# baterry_tester.net
KiCad netlist of a schematic drawn in EAGLE
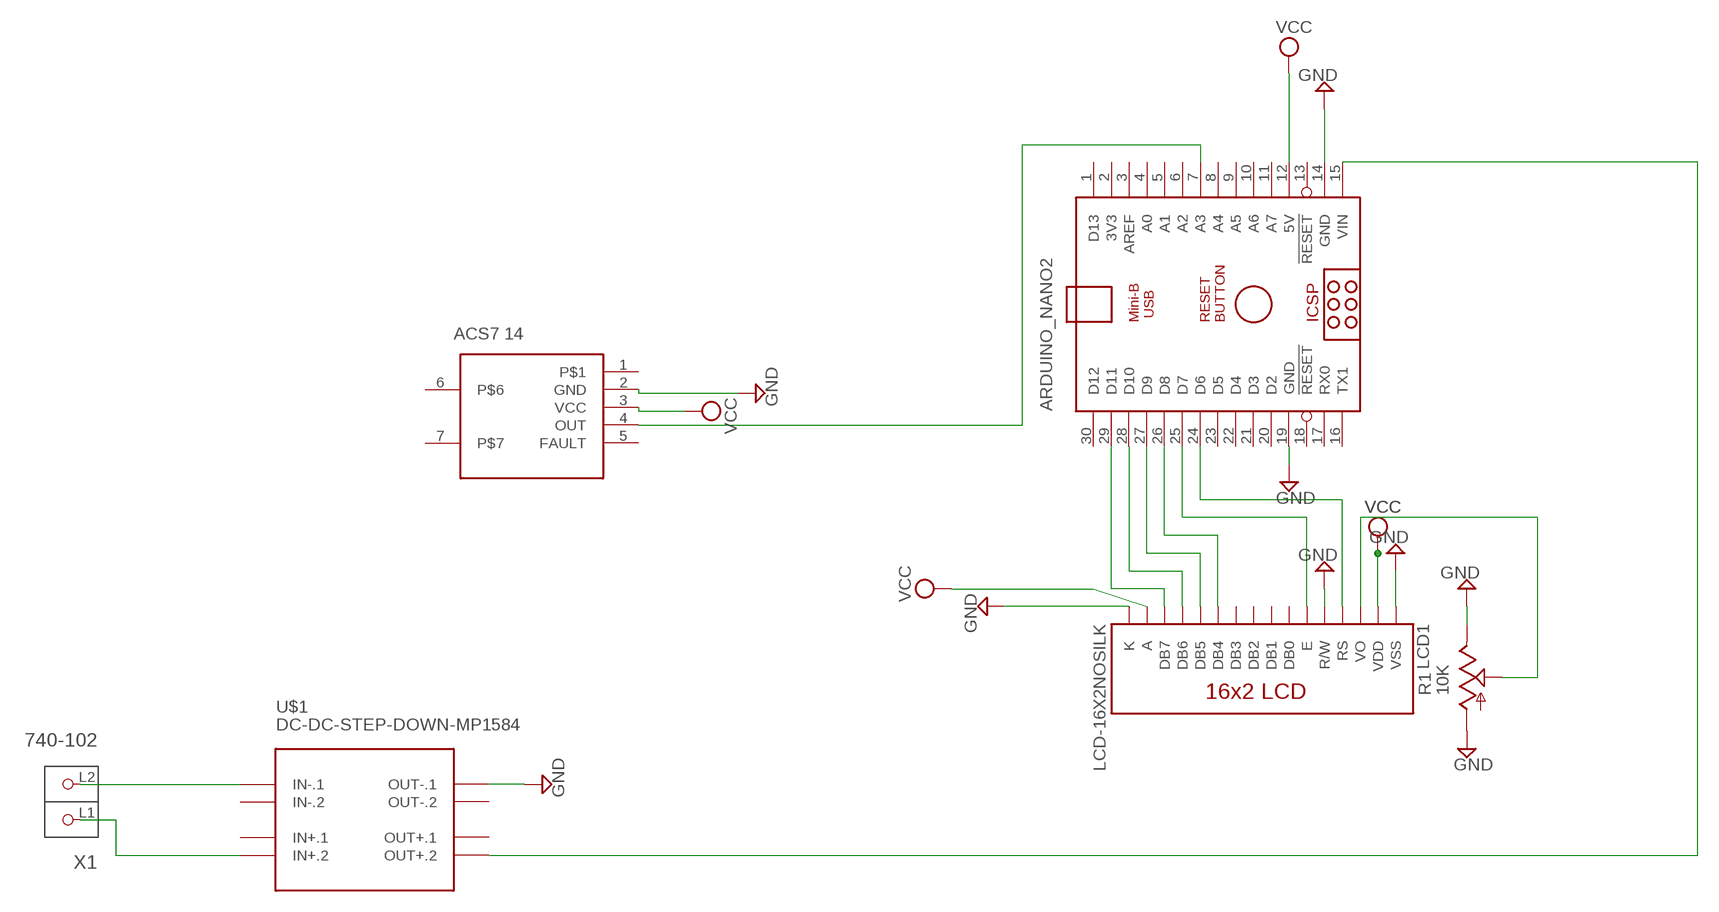
[diagram p0: schematic, sheet 1]

(export (version "E")
  (design (tool "Eeschema 10.0.6"))
  (components
    (comp (ref "ARDUINO_NANO2")
      (value "ARDUINO_NANO")
      (footprint "eagle-import:ARDUINO_NANO")
      (libsource (lib "eagle-import") (part "ARDUINO_NANO"))
    )
    (comp (ref "LCD1")
      (value "LCD-16X2NOSILK")
      (footprint "eagle-import:LCD-16X2_NOSILK")
      (libsource (lib "eagle-import") (part "LCD-16X2NOSILK"))
    )
    (comp (ref "R1")
      (value "10K")
      (footprint "eagle-import:PT-10")
      (libsource (lib "eagle-import") (part "TRIM_US-PT10"))
    )
    (comp (ref "U$1")
      (value "DC-DC-STEP-DOWN-MP1584")
      (footprint "eagle-import:DC-DC-STEP-DOWN-MP1584")
      (libsource (lib "eagle-import") (part "DC-DC-STEP-DOWN-MP1584"))
    )
    (comp (ref "U$3")
      (value "ACS714EGHII-ACS714")
      (footprint "eagle-import:ACS714E")
      (libsource (lib "eagle-import") (part "ACS714EGHII-ACS714"))
    )
    (comp (ref "X1")
      (value "740-102")
      (footprint "eagle-import:P-740-102")
      (libsource (lib "eagle-import") (part "740-102"))
    )
  )
  (nets
    (net (code "1") (name "GND") (class "Default")
      (node (ref "ARDUINO_NANO2") (pin "14") (pinfunction "GND_14") (pintype "power_in"))
      (node (ref "ARDUINO_NANO2") (pin "19") (pinfunction "GND_19") (pintype "power_in"))
      (node (ref "LCD1") (pin "1") (pinfunction "VSS_1") (pintype "power_in"))
      (node (ref "LCD1") (pin "16") (pinfunction "K_16") (pintype "power_in"))
      (node (ref "LCD1") (pin "5") (pinfunction "R/W_5") (pintype "input"))
      (node (ref "R1") (pin "A") (pinfunction "A_A") (pintype "passive"))
      (node (ref "R1") (pin "E") (pinfunction "E_E") (pintype "passive"))
      (node (ref "U$1") (pin "OUT-.1") (pinfunction "OUT-.1_OUT-.1") (pintype "bidirectional"))
      (node (ref "U$3") (pin "2") (pinfunction "GND_2") (pintype "bidirectional"))
    )
    (net (code "2") (name "Net-(ARDUINO_NANO2-A3)") (class "Default")
      (node (ref "ARDUINO_NANO2") (pin "7") (pinfunction "A3_7") (pintype "bidirectional"))
      (node (ref "U$3") (pin "4") (pinfunction "OUT_4") (pintype "bidirectional"))
    )
    (net (code "3") (name "Net-(ARDUINO_NANO2-D6)") (class "Default")
      (node (ref "ARDUINO_NANO2") (pin "24") (pinfunction "D6_24") (pintype "bidirectional"))
      (node (ref "LCD1") (pin "4") (pinfunction "RS_4") (pintype "input"))
    )
    (net (code "4") (name "Net-(ARDUINO_NANO2-D7)") (class "Default")
      (node (ref "ARDUINO_NANO2") (pin "25") (pinfunction "D7_25") (pintype "bidirectional"))
      (node (ref "LCD1") (pin "6") (pinfunction "E_6") (pintype "input"))
    )
    (net (code "5") (name "Net-(ARDUINO_NANO2-D8)") (class "Default")
      (node (ref "ARDUINO_NANO2") (pin "26") (pinfunction "D8_26") (pintype "bidirectional"))
      (node (ref "LCD1") (pin "11") (pinfunction "DB4_11") (pintype "bidirectional"))
    )
    (net (code "6") (name "Net-(ARDUINO_NANO2-D9)") (class "Default")
      (node (ref "ARDUINO_NANO2") (pin "27") (pinfunction "D9_27") (pintype "bidirectional"))
      (node (ref "LCD1") (pin "12") (pinfunction "DB5_12") (pintype "bidirectional"))
    )
    (net (code "7") (name "Net-(ARDUINO_NANO2-D10)") (class "Default")
      (node (ref "ARDUINO_NANO2") (pin "28") (pinfunction "D10_28") (pintype "bidirectional"))
      (node (ref "LCD1") (pin "13") (pinfunction "DB6_13") (pintype "bidirectional"))
    )
    (net (code "8") (name "Net-(ARDUINO_NANO2-D11)") (class "Default")
      (node (ref "ARDUINO_NANO2") (pin "29") (pinfunction "D11_29") (pintype "bidirectional"))
      (node (ref "LCD1") (pin "14") (pinfunction "DB7_14") (pintype "bidirectional"))
    )
    (net (code "9") (name "Net-(ARDUINO_NANO2-VIN)") (class "Default")
      (node (ref "ARDUINO_NANO2") (pin "15") (pinfunction "VIN_15") (pintype "power_in"))
      (node (ref "U$1") (pin "OUT+.2") (pinfunction "OUT+.2_OUT+.2") (pintype "bidirectional"))
    )
    (net (code "10") (name "Net-(LCD1-VO)") (class "Default")
      (node (ref "LCD1") (pin "3") (pinfunction "VO_3") (pintype "bidirectional"))
      (node (ref "R1") (pin "S") (pinfunction "S_S") (pintype "passive"))
    )
    (net (code "11") (name "Net-(X1-P1)") (class "Default")
      (node (ref "U$1") (pin "IN+.2") (pinfunction "IN+.2_IN+.2") (pintype "bidirectional"))
      (node (ref "X1") (pin "L1") (pinfunction "P1_L1") (pintype "bidirectional"))
    )
    (net (code "12") (name "Net-(X1-P2)") (class "Default")
      (node (ref "U$1") (pin "IN-.1") (pinfunction "IN-.1_IN-.1") (pintype "bidirectional"))
      (node (ref "X1") (pin "L2") (pinfunction "P2_L2") (pintype "bidirectional"))
    )
    (net (code "13") (name "VCC") (class "Default")
      (node (ref "ARDUINO_NANO2") (pin "12") (pinfunction "5V_12") (pintype "power_in"))
      (node (ref "LCD1") (pin "15") (pinfunction "A_15") (pintype "power_in"))
      (node (ref "LCD1") (pin "2") (pinfunction "VDD_2") (pintype "power_in"))
      (node (ref "U$3") (pin "3") (pinfunction "VCC_3") (pintype "bidirectional"))
    )
    (net (code "14") (name "unconnected-(ARDUINO_NANO2-3V3-Pad2)") (class "Default")
      (node (ref "ARDUINO_NANO2") (pin "2") (pinfunction "3V3_2") (pintype "output"))
    )
    (net (code "15") (name "unconnected-(ARDUINO_NANO2-A0-Pad4)") (class "Default")
      (node (ref "ARDUINO_NANO2") (pin "4") (pinfunction "A0_4") (pintype "bidirectional"))
    )
    (net (code "16") (name "unconnected-(ARDUINO_NANO2-A1-Pad5)") (class "Default")
      (node (ref "ARDUINO_NANO2") (pin "5") (pinfunction "A1_5") (pintype "bidirectional"))
    )
    (net (code "17") (name "unconnected-(ARDUINO_NANO2-A2-Pad6)") (class "Default")
      (node (ref "ARDUINO_NANO2") (pin "6") (pinfunction "A2_6") (pintype "bidirectional"))
    )
    (net (code "18") (name "unconnected-(ARDUINO_NANO2-A4-Pad8)") (class "Default")
      (node (ref "ARDUINO_NANO2") (pin "8") (pinfunction "A4_8") (pintype "bidirectional"))
    )
    (net (code "19") (name "unconnected-(ARDUINO_NANO2-A5-Pad9)") (class "Default")
      (node (ref "ARDUINO_NANO2") (pin "9") (pinfunction "A5_9") (pintype "bidirectional"))
    )
    (net (code "20") (name "unconnected-(ARDUINO_NANO2-A6-Pad10)") (class "Default")
      (node (ref "ARDUINO_NANO2") (pin "10") (pinfunction "A6_10") (pintype "bidirectional"))
    )
    (net (code "21") (name "unconnected-(ARDUINO_NANO2-A7-Pad11)") (class "Default")
      (node (ref "ARDUINO_NANO2") (pin "11") (pinfunction "A7_11") (pintype "bidirectional"))
    )
    (net (code "22") (name "unconnected-(ARDUINO_NANO2-AREF-Pad3)") (class "Default")
      (node (ref "ARDUINO_NANO2") (pin "3") (pinfunction "AREF_3") (pintype "input"))
    )
    (net (code "23") (name "unconnected-(ARDUINO_NANO2-D2-Pad20)") (class "Default")
      (node (ref "ARDUINO_NANO2") (pin "20") (pinfunction "D2_20") (pintype "bidirectional"))
    )
    (net (code "24") (name "unconnected-(ARDUINO_NANO2-D3-Pad21)") (class "Default")
      (node (ref "ARDUINO_NANO2") (pin "21") (pinfunction "D3_21") (pintype "bidirectional"))
    )
    (net (code "25") (name "unconnected-(ARDUINO_NANO2-D4-Pad22)") (class "Default")
      (node (ref "ARDUINO_NANO2") (pin "22") (pinfunction "D4_22") (pintype "bidirectional"))
    )
    (net (code "26") (name "unconnected-(ARDUINO_NANO2-D5-Pad23)") (class "Default")
      (node (ref "ARDUINO_NANO2") (pin "23") (pinfunction "D5_23") (pintype "bidirectional"))
    )
    (net (code "27") (name "unconnected-(ARDUINO_NANO2-D12-Pad30)") (class "Default")
      (node (ref "ARDUINO_NANO2") (pin "30") (pinfunction "D12_30") (pintype "bidirectional"))
    )
    (net (code "28") (name "unconnected-(ARDUINO_NANO2-D13-Pad1)") (class "Default")
      (node (ref "ARDUINO_NANO2") (pin "1") (pinfunction "D13_1") (pintype "bidirectional"))
    )
    (net (code "29") (name "unconnected-(ARDUINO_NANO2-RX0-Pad17)") (class "Default")
      (node (ref "ARDUINO_NANO2") (pin "17") (pinfunction "RX0_17") (pintype "bidirectional"))
    )
    (net (code "30") (name "unconnected-(ARDUINO_NANO2-TX1-Pad16)") (class "Default")
      (node (ref "ARDUINO_NANO2") (pin "16") (pinfunction "TX1_16") (pintype "bidirectional"))
    )
    (net (code "31") (name "unconnected-(ARDUINO_NANO2-~{RESET}-Pad13)") (class "Default")
      (node (ref "ARDUINO_NANO2") (pin "13") (pinfunction "~{RESET}_13") (pintype "input"))
    )
    (net (code "32") (name "unconnected-(ARDUINO_NANO2-~{RESET}-Pad18)") (class "Default")
      (node (ref "ARDUINO_NANO2") (pin "18") (pinfunction "~{RESET}_18") (pintype "input"))
    )
    (net (code "33") (name "unconnected-(LCD1-DB0-Pad7)") (class "Default")
      (node (ref "LCD1") (pin "7") (pinfunction "DB0_7") (pintype "bidirectional"))
    )
    (net (code "34") (name "unconnected-(LCD1-DB1-Pad8)") (class "Default")
      (node (ref "LCD1") (pin "8") (pinfunction "DB1_8") (pintype "bidirectional"))
    )
    (net (code "35") (name "unconnected-(LCD1-DB2-Pad9)") (class "Default")
      (node (ref "LCD1") (pin "9") (pinfunction "DB2_9") (pintype "bidirectional"))
    )
    (net (code "36") (name "unconnected-(LCD1-DB3-Pad10)") (class "Default")
      (node (ref "LCD1") (pin "10") (pinfunction "DB3_10") (pintype "bidirectional"))
    )
    (net (code "37") (name "unconnected-(U$1-PadIN+.1)") (class "Default")
      (node (ref "U$1") (pin "IN+.1") (pinfunction "IN+.1_IN+.1") (pintype "bidirectional"))
    )
    (net (code "38") (name "unconnected-(U$1-PadIN-.2)") (class "Default")
      (node (ref "U$1") (pin "IN-.2") (pinfunction "IN-.2_IN-.2") (pintype "bidirectional"))
    )
    (net (code "39") (name "unconnected-(U$1-PadOUT+.1)") (class "Default")
      (node (ref "U$1") (pin "OUT+.1") (pinfunction "OUT+.1_OUT+.1") (pintype "bidirectional"))
    )
    (net (code "40") (name "unconnected-(U$1-PadOUT-.2)") (class "Default")
      (node (ref "U$1") (pin "OUT-.2") (pinfunction "OUT-.2_OUT-.2") (pintype "bidirectional"))
    )
    (net (code "41") (name "unconnected-(U$3-FAULT-Pad5)") (class "Default")
      (node (ref "U$3") (pin "5") (pinfunction "FAULT_5") (pintype "bidirectional"))
    )
    (net (code "42") (name "unconnected-(U$3-P$1-Pad1)") (class "Default")
      (node (ref "U$3") (pin "1") (pinfunction "P$1_1") (pintype "bidirectional"))
    )
    (net (code "43") (name "unconnected-(U$3-P$6-Pad6)") (class "Default")
      (node (ref "U$3") (pin "6") (pinfunction "P$6_6") (pintype "bidirectional"))
    )
    (net (code "44") (name "unconnected-(U$3-P$7-Pad7)") (class "Default")
      (node (ref "U$3") (pin "7") (pinfunction "P$7_7") (pintype "bidirectional"))
    )
  )
)
